# pegpixel-pcb.net
KiCad netlist of a schematic drawn in EAGLE
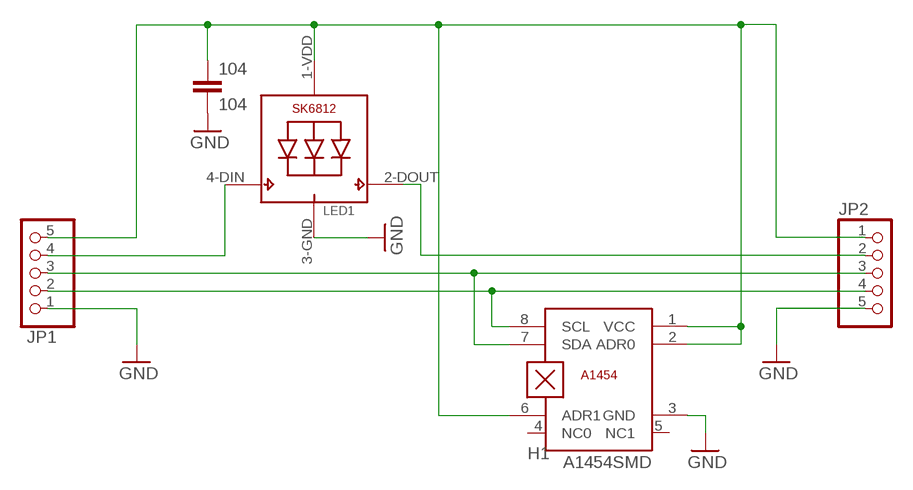
[diagram p0: schematic, sheet 1]

(export (version "E")
  (design (tool "Eeschema 10.0.6"))
  (components
    (comp (ref "104")
      (value "104")
      (footprint "eagle-import:C0805")
      (libsource (lib "eagle-import") (part "C-EUC0805"))
    )
    (comp (ref "H1")
      (value "A1454SMD")
      (footprint "eagle-import:TSSOP8")
      (libsource (lib "eagle-import") (part "A1454SMD"))
    )
    (comp (ref "JP1")
      (value "PINHD-1X5/90")
      (footprint "eagle-import:1X05_90")
      (libsource (lib "eagle-import") (part "PINHD-1X5/90"))
    )
    (comp (ref "JP2")
      (value "PINHD-1X5/90")
      (footprint "eagle-import:1X05_90")
      (libsource (lib "eagle-import") (part "PINHD-1X5/90"))
    )
    (comp (ref "LED1")
      (value "SK6812_5050")
      (footprint "eagle-import:LED5050")
      (libsource (lib "eagle-import") (part "SK6812_5050"))
    )
  )
  (nets
    (net (code "1") (name "GND") (class "Default")
      (node (ref "104") (pin "2") (pinfunction "2_2") (pintype "passive"))
      (node (ref "H1") (pin "3") (pinfunction "GND_3") (pintype "passive"))
      (node (ref "JP1") (pin "1") (pinfunction "1_1") (pintype "passive"))
      (node (ref "JP2") (pin "5") (pinfunction "5_5") (pintype "passive"))
      (node (ref "LED1") (pin "3-GND") (pinfunction "GND_3-GND") (pintype "power_in"))
    )
    (net (code "2") (name "Net-(H1-ADR0)") (class "Default")
      (node (ref "104") (pin "1") (pinfunction "1_1") (pintype "passive"))
      (node (ref "H1") (pin "1") (pinfunction "VCC_1") (pintype "power_in"))
      (node (ref "H1") (pin "2") (pinfunction "ADR0_2") (pintype "input"))
      (node (ref "H1") (pin "6") (pinfunction "ADR1_6") (pintype "input"))
      (node (ref "JP1") (pin "5") (pinfunction "5_5") (pintype "passive"))
      (node (ref "JP2") (pin "1") (pinfunction "1_1") (pintype "passive"))
      (node (ref "LED1") (pin "1-VDD") (pinfunction "VDD_1-VDD") (pintype "power_in"))
    )
    (net (code "3") (name "Net-(H1-SCL)") (class "Default")
      (node (ref "H1") (pin "8") (pinfunction "SCL_8") (pintype "bidirectional"))
      (node (ref "JP1") (pin "2") (pinfunction "2_2") (pintype "passive"))
      (node (ref "JP2") (pin "4") (pinfunction "4_4") (pintype "passive"))
    )
    (net (code "4") (name "Net-(H1-SDA)") (class "Default")
      (node (ref "H1") (pin "7") (pinfunction "SDA_7") (pintype "bidirectional"))
      (node (ref "JP1") (pin "3") (pinfunction "3_3") (pintype "passive"))
      (node (ref "JP2") (pin "3") (pinfunction "3_3") (pintype "passive"))
    )
    (net (code "5") (name "Net-(LED1-DI)") (class "Default")
      (node (ref "JP1") (pin "4") (pinfunction "4_4") (pintype "passive"))
      (node (ref "LED1") (pin "4-DIN") (pinfunction "DI_4-DIN") (pintype "input"))
    )
    (net (code "6") (name "Net-(LED1-DO)") (class "Default")
      (node (ref "JP2") (pin "2") (pinfunction "2_2") (pintype "passive"))
      (node (ref "LED1") (pin "2-DOUT") (pinfunction "DO_2-DOUT") (pintype "output"))
    )
    (net (code "7") (name "unconnected-(H1-NC0-Pad4)") (class "Default")
      (node (ref "H1") (pin "4") (pinfunction "NC0_4") (pintype "no_connect"))
    )
    (net (code "8") (name "unconnected-(H1-NC1-Pad5)") (class "Default")
      (node (ref "H1") (pin "5") (pinfunction "NC1_5") (pintype "no_connect"))
    )
  )
)
